# Buksir_v1_1.net
KiCad netlist of a schematic drawn in EAGLE
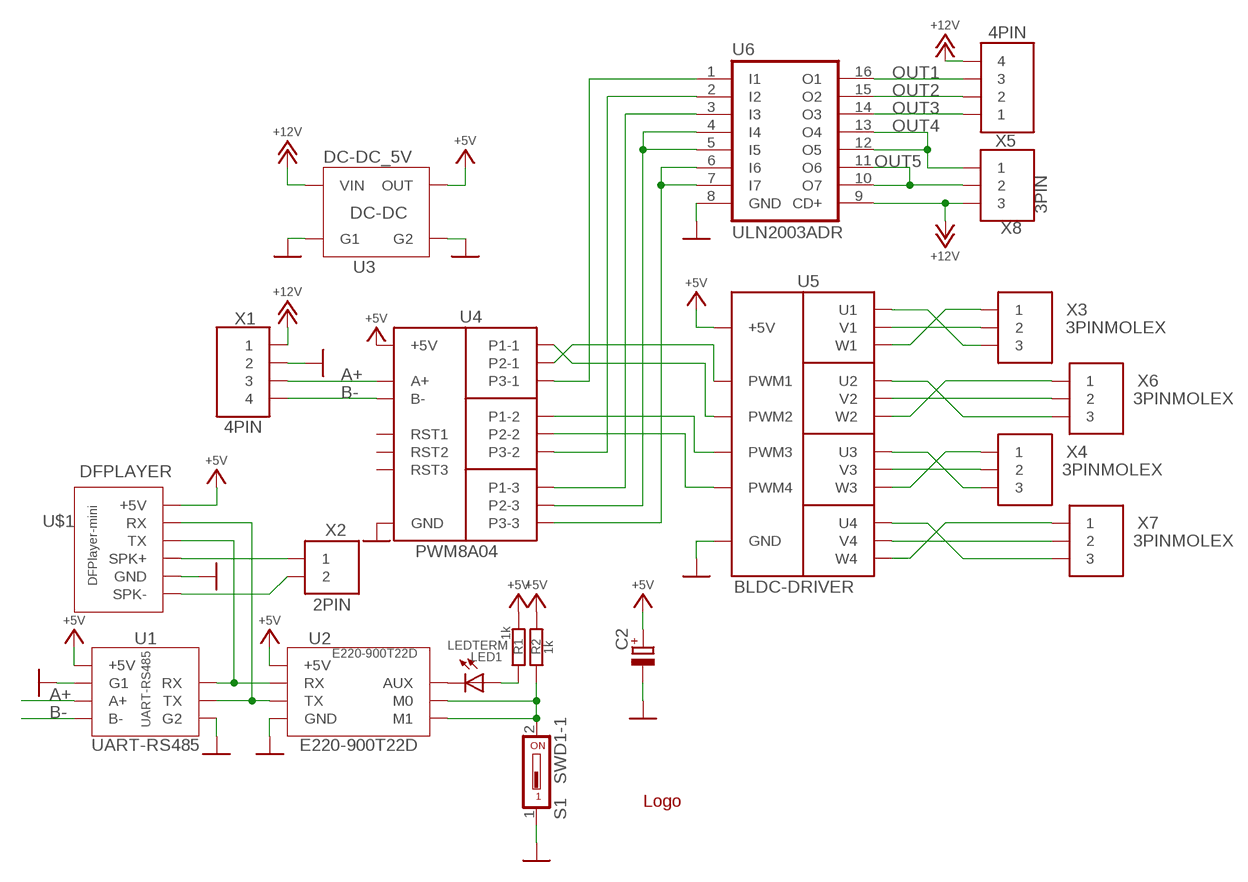
[diagram p0: schematic, sheet 1]

(export (version "E")
  (design (tool "Eeschema 10.0.6"))
  (components
    (comp (ref "C2")
      (value "CAP_POL12")
      (footprint "eagle-import:E3.5-8_R")
      (libsource (lib "eagle-import") (part "CAP_POL12"))
    )
    (comp (ref "LED1")
      (value "LEDTERM")
      (footprint "eagle-import:LED_TERM")
      (libsource (lib "eagle-import") (part "LEDTERM"))
    )
    (comp (ref "R1")
      (value "1k")
      (footprint "eagle-import:R0805")
      (libsource (lib "eagle-import") (part "RESISTOR0805"))
    )
    (comp (ref "R2")
      (value "1k")
      (footprint "eagle-import:R0805")
      (libsource (lib "eagle-import") (part "RESISTOR0805"))
    )
    (comp (ref "S1")
      (value "SWD1-1")
      (footprint "eagle-import:DS-01")
      (libsource (lib "eagle-import") (part "DS01"))
    )
    (comp (ref "U$1")
      (value "DFPLAYER")
      (footprint "eagle-import:MP3-PLAYER")
      (libsource (lib "eagle-import") (part "DFPLAYER"))
    )
    (comp (ref "U$2")
      (value "LOGO")
      (footprint "eagle-import:LOGO")
      (libsource (lib "eagle-import") (part "LOGO"))
    )
    (comp (ref "U1")
      (value "UART-RS485")
      (footprint "eagle-import:UART-RS485")
      (libsource (lib "eagle-import") (part "UART-RS485"))
    )
    (comp (ref "U2")
      (value "E220-900T22D")
      (footprint "eagle-import:E220-900T22D")
      (libsource (lib "eagle-import") (part "E220-900T22D"))
    )
    (comp (ref "U3")
      (value "DC-DC_5V")
      (footprint "eagle-import:DC-DC_5V")
      (libsource (lib "eagle-import") (part "DC-DC_5V"))
    )
    (comp (ref "U4")
      (value "PWM8A04")
      (footprint "eagle-import:PWM8A04")
      (libsource (lib "eagle-import") (part "PWM8A04"))
    )
    (comp (ref "U5")
      (value "BLDC-DRIVER")
      (footprint "eagle-import:BLDC-DRIVER")
      (libsource (lib "eagle-import") (part "BLDC-DRIVER"))
    )
    (comp (ref "U6")
      (value "ULN2003ADR")
      (footprint "eagle-import:SOIC-16")
      (libsource (lib "eagle-import") (part "ULN2003ADR"))
    )
    (comp (ref "X1")
      (value "4PIN")
      (footprint "eagle-import:4PIN-2.5MM")
      (libsource (lib "eagle-import") (part "4PIN"))
    )
    (comp (ref "X2")
      (value "2PIN")
      (footprint "eagle-import:2PIN-2.5MM")
      (libsource (lib "eagle-import") (part "2PIN"))
    )
    (comp (ref "X3")
      (value "3PINMOLEX")
      (footprint "eagle-import:3PIN-MOLEX")
      (libsource (lib "eagle-import") (part "3PINMOLEX"))
    )
    (comp (ref "X4")
      (value "3PINMOLEX")
      (footprint "eagle-import:3PIN-MOLEX")
      (libsource (lib "eagle-import") (part "3PINMOLEX"))
    )
    (comp (ref "X5")
      (value "4PIN")
      (footprint "eagle-import:4PIN-2.5MM")
      (libsource (lib "eagle-import") (part "4PIN"))
    )
    (comp (ref "X6")
      (value "3PINMOLEX")
      (footprint "eagle-import:3PIN-MOLEX")
      (libsource (lib "eagle-import") (part "3PINMOLEX"))
    )
    (comp (ref "X7")
      (value "3PINMOLEX")
      (footprint "eagle-import:3PIN-MOLEX")
      (libsource (lib "eagle-import") (part "3PINMOLEX"))
    )
    (comp (ref "X8")
      (value "3PIN")
      (footprint "eagle-import:3PIN-2.5MM")
      (libsource (lib "eagle-import") (part "3PIN"))
    )
  )
  (nets
    (net (code "1") (name "+5V") (class "Default")
      (node (ref "C2") (pin "+") (pinfunction "+_+") (pintype "passive"))
      (node (ref "R1") (pin "2") (pinfunction "2_2") (pintype "passive"))
      (node (ref "R2") (pin "2") (pinfunction "2_2") (pintype "passive"))
      (node (ref "U$1") (pin "VCC") (pinfunction "+5V_VCC") (pintype "bidirectional"))
      (node (ref "U1") (pin "VCC") (pinfunction "+5V_VCC") (pintype "bidirectional"))
      (node (ref "U2") (pin "VCC") (pinfunction "+5V_VCC") (pintype "bidirectional"))
      (node (ref "U3") (pin "OUT") (pinfunction "OUT_OUT") (pintype "bidirectional"))
      (node (ref "U4") (pin "+V") (pinfunction "+5V_+V") (pintype "bidirectional"))
      (node (ref "U5") (pin "B+") (pinfunction "+5V_B+") (pintype "bidirectional"))
    )
    (net (code "2") (name "+12V") (class "Default")
      (node (ref "U3") (pin "VIN") (pinfunction "VIN_VIN") (pintype "bidirectional"))
      (node (ref "U6") (pin "9") (pinfunction "CD+_9") (pintype "passive"))
      (node (ref "X1") (pin "P$4") (pinfunction "1_P$4") (pintype "bidirectional"))
      (node (ref "X5") (pin "P$1") (pinfunction "4_P$1") (pintype "bidirectional"))
      (node (ref "X8") (pin "P$3") (pinfunction "3_P$3") (pintype "bidirectional"))
    )
    (net (code "3") (name "/A+") (class "Default")
      (node (ref "U1") (pin "A+") (pinfunction "A+_A+") (pintype "bidirectional"))
      (node (ref "U4") (pin "A+") (pinfunction "A+_A+") (pintype "bidirectional"))
      (node (ref "X1") (pin "P$2") (pinfunction "3_P$2") (pintype "bidirectional"))
    )
    (net (code "4") (name "/B-") (class "Default")
      (node (ref "U1") (pin "B-") (pinfunction "B-_B-") (pintype "bidirectional"))
      (node (ref "U4") (pin "B-") (pinfunction "B-_B-") (pintype "bidirectional"))
      (node (ref "X1") (pin "P$1") (pinfunction "4_P$1") (pintype "bidirectional"))
    )
    (net (code "5") (name "/OUT1") (class "Default")
      (node (ref "U6") (pin "16") (pinfunction "O1_16") (pintype "open_collector"))
      (node (ref "X5") (pin "P$2") (pinfunction "3_P$2") (pintype "bidirectional"))
    )
    (net (code "6") (name "/OUT2") (class "Default")
      (node (ref "U6") (pin "15") (pinfunction "O2_15") (pintype "open_collector"))
      (node (ref "X5") (pin "P$3") (pinfunction "2_P$3") (pintype "bidirectional"))
    )
    (net (code "7") (name "/OUT3") (class "Default")
      (node (ref "U6") (pin "14") (pinfunction "O3_14") (pintype "open_collector"))
      (node (ref "X5") (pin "P$4") (pinfunction "1_P$4") (pintype "bidirectional"))
    )
    (net (code "8") (name "/OUT4") (class "Default")
      (node (ref "U6") (pin "12") (pinfunction "O5_12") (pintype "open_collector"))
      (node (ref "U6") (pin "13") (pinfunction "O4_13") (pintype "open_collector"))
      (node (ref "X8") (pin "P$1") (pinfunction "1_P$1") (pintype "bidirectional"))
    )
    (net (code "9") (name "/OUT5") (class "Default")
      (node (ref "U6") (pin "10") (pinfunction "O7_10") (pintype "open_collector"))
      (node (ref "U6") (pin "11") (pinfunction "O6_11") (pintype "open_collector"))
      (node (ref "X8") (pin "P$2") (pinfunction "2_P$2") (pintype "bidirectional"))
    )
    (net (code "10") (name "GND") (class "Default")
      (node (ref "C2") (pin "-") (pinfunction "-_-") (pintype "passive"))
      (node (ref "S1") (pin "1") (pinfunction "1_1") (pintype "passive"))
      (node (ref "U$1") (pin "GND") (pinfunction "GND_GND") (pintype "bidirectional"))
      (node (ref "U1") (pin "G1") (pinfunction "G1_G1") (pintype "bidirectional"))
      (node (ref "U1") (pin "G2") (pinfunction "G2_G2") (pintype "bidirectional"))
      (node (ref "U2") (pin "GND") (pinfunction "GND_GND") (pintype "bidirectional"))
      (node (ref "U3") (pin "G1") (pinfunction "G1_G1") (pintype "bidirectional"))
      (node (ref "U3") (pin "G2") (pinfunction "G2_G2") (pintype "bidirectional"))
      (node (ref "U4") (pin "GND") (pinfunction "GND_GND") (pintype "bidirectional"))
      (node (ref "U5") (pin "B-") (pinfunction "GND_B-") (pintype "bidirectional"))
      (node (ref "U6") (pin "8") (pinfunction "GND_8") (pintype "power_in"))
      (node (ref "X1") (pin "P$3") (pinfunction "2_P$3") (pintype "bidirectional"))
    )
    (net (code "11") (name "Net-(LED1-C)") (class "Default")
      (node (ref "LED1") (pin "K") (pinfunction "C_K") (pintype "passive"))
      (node (ref "U2") (pin "AUX") (pinfunction "AUX_AUX") (pintype "bidirectional"))
    )
    (net (code "12") (name "Net-(LED1-PadA)") (class "Default")
      (node (ref "LED1") (pin "A") (pinfunction "A_A") (pintype "passive"))
      (node (ref "R1") (pin "1") (pinfunction "1_1") (pintype "passive"))
    )
    (net (code "13") (name "Net-(R2-Pad1)") (class "Default")
      (node (ref "R2") (pin "1") (pinfunction "1_1") (pintype "passive"))
      (node (ref "S1") (pin "2") (pinfunction "2_2") (pintype "passive"))
      (node (ref "U2") (pin "M0") (pinfunction "M0_M0") (pintype "bidirectional"))
      (node (ref "U2") (pin "M1") (pinfunction "M1_M1") (pintype "bidirectional"))
    )
    (net (code "14") (name "Net-(U$1-SPK+)") (class "Default")
      (node (ref "U$1") (pin "S+") (pinfunction "SPK+_S+") (pintype "bidirectional"))
      (node (ref "X2") (pin "P$1") (pinfunction "1_P$1") (pintype "bidirectional"))
    )
    (net (code "15") (name "Net-(U$1-SPK-)") (class "Default")
      (node (ref "U$1") (pin "S-") (pinfunction "SPK-_S-") (pintype "bidirectional"))
      (node (ref "X2") (pin "P$2") (pinfunction "2_P$2") (pintype "bidirectional"))
    )
    (net (code "16") (name "Net-(U2-RX)") (class "Default")
      (node (ref "U$1") (pin "TX") (pinfunction "TX_TX") (pintype "bidirectional"))
      (node (ref "U1") (pin "RX") (pinfunction "RX_RX") (pintype "bidirectional"))
      (node (ref "U2") (pin "RXD") (pinfunction "RX_RXD") (pintype "bidirectional"))
    )
    (net (code "17") (name "Net-(U2-TX)") (class "Default")
      (node (ref "U$1") (pin "RX") (pinfunction "RX_RX") (pintype "bidirectional"))
      (node (ref "U1") (pin "TX") (pinfunction "TX_TX") (pintype "bidirectional"))
      (node (ref "U2") (pin "TXD") (pinfunction "TX_TXD") (pintype "bidirectional"))
    )
    (net (code "18") (name "Net-(U4-PadP1-1)") (class "Default")
      (node (ref "U4") (pin "P1-1") (pinfunction "P1-1_P1-1") (pintype "bidirectional"))
      (node (ref "U5") (pin "PWM2") (pinfunction "PWM2_PWM2") (pintype "bidirectional"))
    )
    (net (code "19") (name "Net-(U4-PadP1-2)") (class "Default")
      (node (ref "U4") (pin "P1-2") (pinfunction "P1-2_P1-2") (pintype "bidirectional"))
      (node (ref "U5") (pin "PWM3") (pinfunction "PWM3_PWM3") (pintype "bidirectional"))
    )
    (net (code "20") (name "Net-(U4-PadP2-1)") (class "Default")
      (node (ref "U4") (pin "P2-1") (pinfunction "P2-1_P2-1") (pintype "bidirectional"))
      (node (ref "U5") (pin "PWM1") (pinfunction "PWM1_PWM1") (pintype "bidirectional"))
    )
    (net (code "21") (name "Net-(U4-PadP2-2)") (class "Default")
      (node (ref "U4") (pin "P2-2") (pinfunction "P2-2_P2-2") (pintype "bidirectional"))
      (node (ref "U5") (pin "PWM4") (pinfunction "PWM4_PWM4") (pintype "bidirectional"))
    )
    (net (code "22") (name "Net-(U6-I1)") (class "Default")
      (node (ref "U4") (pin "P3-1") (pinfunction "P3-1_P3-1") (pintype "bidirectional"))
      (node (ref "U6") (pin "1") (pinfunction "I1_1") (pintype "input"))
    )
    (net (code "23") (name "Net-(U6-I2)") (class "Default")
      (node (ref "U4") (pin "P3-2") (pinfunction "P3-2_P3-2") (pintype "bidirectional"))
      (node (ref "U6") (pin "2") (pinfunction "I2_2") (pintype "input"))
    )
    (net (code "24") (name "Net-(U6-I3)") (class "Default")
      (node (ref "U4") (pin "P1-3") (pinfunction "P1-3_P1-3") (pintype "bidirectional"))
      (node (ref "U6") (pin "3") (pinfunction "I3_3") (pintype "input"))
    )
    (net (code "25") (name "Net-(U6-I4)") (class "Default")
      (node (ref "U4") (pin "P2-3") (pinfunction "P2-3_P2-3") (pintype "bidirectional"))
      (node (ref "U6") (pin "4") (pinfunction "I4_4") (pintype "input"))
      (node (ref "U6") (pin "5") (pinfunction "I5_5") (pintype "input"))
    )
    (net (code "26") (name "Net-(U6-I6)") (class "Default")
      (node (ref "U4") (pin "P3-3") (pinfunction "P3-3_P3-3") (pintype "bidirectional"))
      (node (ref "U6") (pin "6") (pinfunction "I6_6") (pintype "input"))
      (node (ref "U6") (pin "7") (pinfunction "I7_7") (pintype "input"))
    )
    (net (code "27") (name "Net-(X3-1)") (class "Default")
      (node (ref "U5") (pin "W1") (pinfunction "W1_W1") (pintype "bidirectional"))
      (node (ref "X3") (pin "P$1") (pinfunction "1_P$1") (pintype "bidirectional"))
    )
    (net (code "28") (name "Net-(X3-2)") (class "Default")
      (node (ref "U5") (pin "V1") (pinfunction "V1_V1") (pintype "bidirectional"))
      (node (ref "X3") (pin "P$2") (pinfunction "2_P$2") (pintype "bidirectional"))
    )
    (net (code "29") (name "Net-(X3-3)") (class "Default")
      (node (ref "U5") (pin "U1") (pinfunction "U1_U1") (pintype "bidirectional"))
      (node (ref "X3") (pin "P$3") (pinfunction "3_P$3") (pintype "bidirectional"))
    )
    (net (code "30") (name "Net-(X4-1)") (class "Default")
      (node (ref "U5") (pin "W3") (pinfunction "W3_W3") (pintype "bidirectional"))
      (node (ref "X4") (pin "P$1") (pinfunction "1_P$1") (pintype "bidirectional"))
    )
    (net (code "31") (name "Net-(X4-2)") (class "Default")
      (node (ref "U5") (pin "V3") (pinfunction "V3_V3") (pintype "bidirectional"))
      (node (ref "X4") (pin "P$2") (pinfunction "2_P$2") (pintype "bidirectional"))
    )
    (net (code "32") (name "Net-(X4-3)") (class "Default")
      (node (ref "U5") (pin "U3") (pinfunction "U3_U3") (pintype "bidirectional"))
      (node (ref "X4") (pin "P$3") (pinfunction "3_P$3") (pintype "bidirectional"))
    )
    (net (code "33") (name "Net-(X6-1)") (class "Default")
      (node (ref "U5") (pin "W2") (pinfunction "W2_W2") (pintype "bidirectional"))
      (node (ref "X6") (pin "P$1") (pinfunction "1_P$1") (pintype "bidirectional"))
    )
    (net (code "34") (name "Net-(X6-2)") (class "Default")
      (node (ref "U5") (pin "V2") (pinfunction "V2_V2") (pintype "bidirectional"))
      (node (ref "X6") (pin "P$2") (pinfunction "2_P$2") (pintype "bidirectional"))
    )
    (net (code "35") (name "Net-(X6-3)") (class "Default")
      (node (ref "U5") (pin "U2") (pinfunction "U2_U2") (pintype "bidirectional"))
      (node (ref "X6") (pin "P$3") (pinfunction "3_P$3") (pintype "bidirectional"))
    )
    (net (code "36") (name "Net-(X7-1)") (class "Default")
      (node (ref "U5") (pin "W4") (pinfunction "W4_W4") (pintype "bidirectional"))
      (node (ref "X7") (pin "P$1") (pinfunction "1_P$1") (pintype "bidirectional"))
    )
    (net (code "37") (name "Net-(X7-2)") (class "Default")
      (node (ref "U5") (pin "V4") (pinfunction "V4_V4") (pintype "bidirectional"))
      (node (ref "X7") (pin "P$2") (pinfunction "2_P$2") (pintype "bidirectional"))
    )
    (net (code "38") (name "Net-(X7-3)") (class "Default")
      (node (ref "U5") (pin "U4") (pinfunction "U4_U4") (pintype "bidirectional"))
      (node (ref "X7") (pin "P$3") (pinfunction "3_P$3") (pintype "bidirectional"))
    )
    (net (code "39") (name "unconnected-(U4-PadRST1)") (class "Default")
      (node (ref "U4") (pin "RST1") (pinfunction "RST1_RST1") (pintype "bidirectional"))
    )
    (net (code "40") (name "unconnected-(U4-PadRST2)") (class "Default")
      (node (ref "U4") (pin "RST2") (pinfunction "RST2_RST2") (pintype "bidirectional"))
    )
    (net (code "41") (name "unconnected-(U4-PadRST3)") (class "Default")
      (node (ref "U4") (pin "RST3") (pinfunction "RST3_RST3") (pintype "bidirectional"))
    )
  )
)
